# Connections.net
KiCad netlist of a schematic drawn in Altium Designer
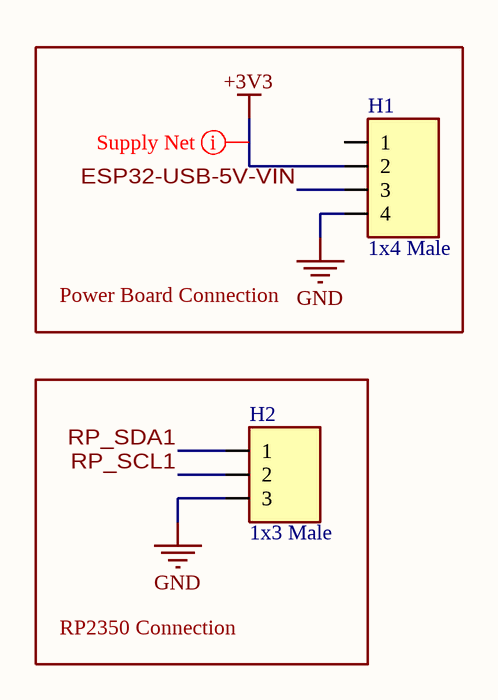
[diagram p0: Connections.SchDoc]

(export (version "E")
  (design (tool "Eeschema 10.0.6"))
  (components
    (comp (ref "H1")
      (value "1x4 Male")
      (footprint "[Header] Shrouded 1x4 Male")
      (description "70543-0003\r\nMates with 005057-9404")
      (libsource (lib "RADM Connectors") (part "[Header] Shrouded 1x4 Male"))
    )
    (comp (ref "H2")
      (value "1x3 Male")
      (footprint "[Header] Shrouded 1x3 Male")
      (description "070543-0037\r\nMates with 005057-9403")
      (libsource (lib "RADM Connectors") (part "[Header] Shrouded 1x3 Male"))
    )
  )
  (nets
    (net (code "1") (name "+3V3") (class "Default")
      (node (ref "H1") (pin "2") (pinfunction "2_2") (pintype "passive"))
    )
    (net (code "2") (name "/ESP32-USB-5V-VIN") (class "Default")
      (node (ref "H1") (pin "3") (pinfunction "3_3") (pintype "passive"))
    )
    (net (code "3") (name "/RP_SCL1") (class "Default")
      (node (ref "H2") (pin "2") (pinfunction "2_2") (pintype "passive"))
    )
    (net (code "4") (name "/RP_SDA1") (class "Default")
      (node (ref "H2") (pin "1") (pinfunction "1_1") (pintype "passive"))
    )
    (net (code "5") (name "GND") (class "Default")
      (node (ref "H1") (pin "4") (pinfunction "4_4") (pintype "passive"))
      (node (ref "H2") (pin "3") (pinfunction "3_3") (pintype "passive"))
    )
    (net (code "6") (name "unconnected-(H1-Pad1)") (class "Default")
      (node (ref "H1") (pin "1") (pinfunction "1_1") (pintype "passive"))
    )
  )
)
